# ir.net
KiCad netlist of a schematic drawn in EAGLE
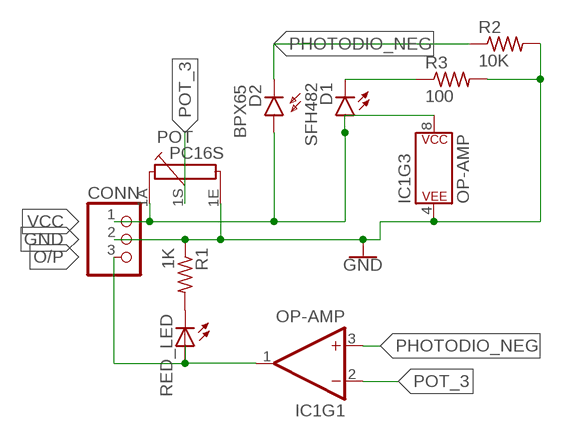
[diagram p0: schematic, sheet 1]

(export (version "E")
  (design (tool "Eeschema 10.0.6"))
  (components
    (comp (ref "CONN")
      (value "PINHD-1X3")
      (footprint "eagle-import:1X03")
      (libsource (lib "eagle-import") (part "PINHD-1X3"))
    )
    (comp (ref "D1")
      (value "SFH482")
      (footprint "eagle-import:SFH482")
      (libsource (lib "eagle-import") (part "SFH482"))
    )
    (comp (ref "D2")
      (value "BPX65")
      (footprint "eagle-import:BPX65")
      (fields (field (name "MPN") "BPX65."))
      (libsource (lib "eagle-import") (part "BPX65"))
    )
    (comp (ref "IC1")
      (value "OP-AMP")
      (footprint "eagle-import:DIP08")
      (libsource (lib "eagle-import") (part "OPAMP-DUALDIP"))
    )
    (comp (ref "POT")
      (value "PC16S")
      (footprint "eagle-import:PC16S")
      (libsource (lib "eagle-import") (part "PC16S"))
    )
    (comp (ref "R1")
      (value "1K")
      (footprint "eagle-import:0805-THM")
      (libsource (lib "eagle-import") (part "FLIPFLOP-RES"))
    )
    (comp (ref "R2")
      (value "10K")
      (footprint "eagle-import:0805-THM")
      (libsource (lib "eagle-import") (part "FLIPFLOP-RES"))
    )
    (comp (ref "R3")
      (value "100")
      (footprint "eagle-import:0805-THM")
      (libsource (lib "eagle-import") (part "FLIPFLOP-RES"))
    )
    (comp (ref "RED_LED")
      (value "LED3MM")
      (footprint "eagle-import:LED3MM")
      (libsource (lib "eagle-import") (part "LED3MM"))
    )
  )
  (nets
    (net (code "1") (name "GND") (class "Default")
      (node (ref "CONN") (pin "2") (pinfunction "2_2") (pintype "passive"))
      (node (ref "IC1") (pin "4") (pinfunction "P$V-_4") (pintype "bidirectional"))
      (node (ref "POT") (pin "1E") (pinfunction "1E_1E") (pintype "passive"))
      (node (ref "R1") (pin "1") (pinfunction "1_1") (pintype "passive"))
      (node (ref "R2") (pin "2") (pinfunction "2_2") (pintype "passive"))
      (node (ref "R3") (pin "2") (pinfunction "2_2") (pintype "passive"))
    )
    (net (code "2") (name "Net-(D1-C)") (class "Default")
      (node (ref "D1") (pin "K") (pinfunction "C_K") (pintype "passive"))
      (node (ref "R3") (pin "1") (pinfunction "1_1") (pintype "passive"))
    )
    (net (code "3") (name "Net-(RED_LED-C)") (class "Default")
      (node (ref "R1") (pin "2") (pinfunction "2_2") (pintype "passive"))
      (node (ref "RED_LED") (pin "K") (pinfunction "C_K") (pintype "passive"))
    )
    (net (code "4") (name "O{slash}P") (class "Default")
      (node (ref "CONN") (pin "3") (pinfunction "3_3") (pintype "passive"))
      (node (ref "IC1") (pin "1") (pinfunction "OUT_1") (pintype "output"))
      (node (ref "RED_LED") (pin "A") (pinfunction "A_A") (pintype "passive"))
    )
    (net (code "5") (name "PHOTODIO_NEG") (class "Default")
      (node (ref "D2") (pin "K") (pinfunction "C_K") (pintype "passive"))
      (node (ref "IC1") (pin "3") (pinfunction "+IN_3") (pintype "input"))
      (node (ref "R2") (pin "1") (pinfunction "1_1") (pintype "passive"))
    )
    (net (code "6") (name "POT_3") (class "Default")
      (node (ref "IC1") (pin "2") (pinfunction "-IN_2") (pintype "input"))
      (node (ref "POT") (pin "1S") (pinfunction "1S_1S") (pintype "passive"))
    )
    (net (code "7") (name "VCC") (class "Default")
      (node (ref "CONN") (pin "1") (pinfunction "1_1") (pintype "passive"))
      (node (ref "D1") (pin "A") (pinfunction "A_A") (pintype "passive"))
      (node (ref "D2") (pin "A") (pinfunction "A_A") (pintype "passive"))
      (node (ref "IC1") (pin "8") (pinfunction "P$V+_8") (pintype "bidirectional"))
      (node (ref "POT") (pin "1A") (pinfunction "1A_1A") (pintype "passive"))
    )
  )
)
